# CVC_power.net
KiCad netlist of a schematic drawn in Altium Designer
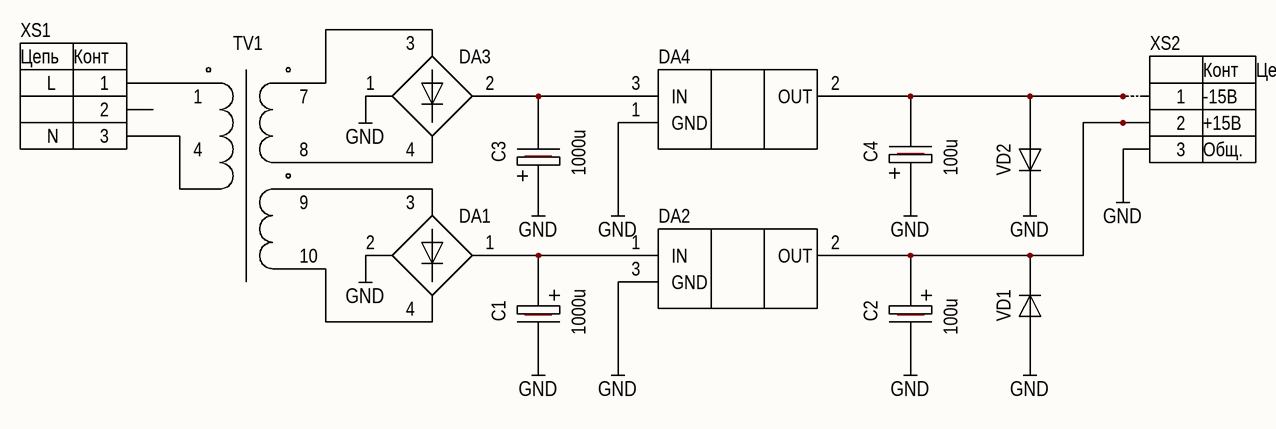
[diagram p0: CVC_power.SchDoc]

(export (version "E")
  (design (tool "Eeschema 10.0.6"))
  (components
    (comp (ref "C1")
      (value "Конденсатор К50-68")
      (footprint "CAPPR5-13x20")
      (description "Электролитический конденсатор")
      (fields (field (name "LABEL") "1000u"))
      (libsource (lib "") (part "Конденсатор К50-68_1"))
    )
    (comp (ref "C2")
      (value "Конденсатор К50-68")
      (footprint "CAPPR5-13x20")
      (description "Электролитический конденсатор")
      (fields (field (name "LABEL") "100u"))
      (libsource (lib "") (part "Конденсатор К50-68_1"))
    )
    (comp (ref "C3")
      (value "Конденсатор К50-68")
      (footprint "CAPPR5-13x20")
      (description "Электролитический конденсатор")
      (fields (field (name "LABEL") "1000u"))
      (libsource (lib "CVC_power") (part "Конденсатор К50-68"))
    )
    (comp (ref "C4")
      (value "Конденсатор К50-68")
      (footprint "CAPPR5-13x20")
      (description "Электролитический конденсатор")
      (fields (field (name "LABEL") "100u"))
      (libsource (lib "CVC_power") (part "Конденсатор К50-68"))
    )
    (comp (ref "DA1")
      (value "диодный мост")
      (footprint "DF08M")
      (libsource (lib "CVC_power") (part "Мост DB08M"))
    )
    (comp (ref "DA2")
      (value "L7815ACV")
      (footprint "TO220ABN")
      (libsource (lib "CVC_power") (part "L7815ACV"))
    )
    (comp (ref "DA3")
      (value "диодный мост")
      (footprint "DF08M")
      (libsource (lib "CVC_power") (part "Мост DB08M"))
    )
    (comp (ref "DA4") (value "L7915ACV") (footprint "TO220V") (libsource (lib "CVC_power") (part "L7915ACV")))
    (comp (ref "TV1")
      (value "Трансформатор ТП 112/ТПК-2")
      (footprint "Transformer TP 112/TPK - 2")
      (libsource (lib "CVC_power") (part "Трансформатор ТП 112/ТПК-2"))
    )
    (comp (ref "VD1") (value "1N4001") (footprint "DO-41") (libsource (lib "CVC_power") (part "1N4001")))
    (comp (ref "VD2") (value "1N4001") (footprint "DO-41") (libsource (lib "CVC_power") (part "1N4001")))
    (comp (ref "XS1")
      (value "Клемма 15EDGRC-3.81-03P (XY2500R)")
      (footprint "15EDGRC-3.81-03P")
      (libsource (lib "CVC_power") (part "Клемма 15EDGRC-3.81-03P (XY2500R)"))
    )
    (comp (ref "XS2")
      (value "Клемма 15EDGRC-3.81-03P (XY2500R)")
      (footprint "15EDGRC-3.81-03P")
      (libsource (lib "CVC_power") (part "Клемма 15EDGRC-3.81-03P (XY2500R)"))
    )
  )
  (nets
    (net (code "1") (name "+15V") (class "Default")
      (node (ref "C2") (pin "1") (pinfunction "+_1") (pintype "passive"))
      (node (ref "DA2") (pin "2") (pinfunction "OUT_2") (pintype "power_in"))
      (node (ref "VD1") (pin "2") (pinfunction "K_2") (pintype "passive"))
      (node (ref "XS2") (pin "2") (pinfunction "2_2") (pintype "passive"))
    )
    (net (code "2") (name "-15V") (class "Default")
      (node (ref "C4") (pin "2") (pinfunction "-_2") (pintype "passive"))
      (node (ref "DA4") (pin "2") (pinfunction "OUT_2") (pintype "power_in"))
      (node (ref "VD2") (pin "1") (pinfunction "A_1") (pintype "passive"))
      (node (ref "XS2") (pin "1") (pinfunction "1_1") (pintype "passive"))
    )
    (net (code "3") (name "GND") (class "Default")
      (node (ref "C1") (pin "2") (pinfunction "-_2") (pintype "passive"))
      (node (ref "C2") (pin "2") (pinfunction "-_2") (pintype "passive"))
      (node (ref "C3") (pin "1") (pinfunction "+_1") (pintype "passive"))
      (node (ref "C4") (pin "1") (pinfunction "+_1") (pintype "passive"))
      (node (ref "DA1") (pin "2") (pinfunction "-_2") (pintype "passive"))
      (node (ref "DA2") (pin "3") (pinfunction "GND_3") (pintype "power_in"))
      (node (ref "DA3") (pin "1") (pinfunction "+_1") (pintype "passive"))
      (node (ref "DA4") (pin "1") (pinfunction "GND_1") (pintype "power_in"))
      (node (ref "VD1") (pin "1") (pinfunction "A_1") (pintype "passive"))
      (node (ref "VD2") (pin "2") (pinfunction "K_2") (pintype "passive"))
      (node (ref "XS2") (pin "3") (pinfunction "3_3") (pintype "passive"))
    )
    (net (code "4") (name "Net-(C1-+)") (class "Default")
      (node (ref "C1") (pin "1") (pinfunction "+_1") (pintype "passive"))
      (node (ref "DA1") (pin "1") (pinfunction "+_1") (pintype "passive"))
      (node (ref "DA2") (pin "1") (pinfunction "IN_1") (pintype "power_in"))
    )
    (net (code "5") (name "Net-(C3--)") (class "Default")
      (node (ref "C3") (pin "2") (pinfunction "-_2") (pintype "passive"))
      (node (ref "DA3") (pin "2") (pinfunction "-_2") (pintype "passive"))
      (node (ref "DA4") (pin "3") (pinfunction "IN_3") (pintype "power_in"))
    )
    (net (code "6") (name "Net-(TV1-P1)") (class "Default")
      (node (ref "TV1") (pin "1") (pinfunction "P1_1") (pintype "passive"))
      (node (ref "XS1") (pin "1") (pinfunction "1_1") (pintype "passive"))
    )
    (net (code "7") (name "Net-(TV1-P4)") (class "Default")
      (node (ref "TV1") (pin "4") (pinfunction "P4_4") (pintype "passive"))
      (node (ref "XS1") (pin "3") (pinfunction "3_3") (pintype "passive"))
    )
    (net (code "8") (name "Net-(TV1-S7)") (class "Default")
      (node (ref "DA3") (pin "3") (pinfunction "~_3") (pintype "passive"))
      (node (ref "TV1") (pin "7") (pinfunction "S7_7") (pintype "passive"))
    )
    (net (code "9") (name "Net-(TV1-S8)") (class "Default")
      (node (ref "DA3") (pin "4") (pinfunction "~_4") (pintype "passive"))
      (node (ref "TV1") (pin "8") (pinfunction "S8_8") (pintype "passive"))
    )
    (net (code "10") (name "Net-(TV1-S9)") (class "Default")
      (node (ref "DA1") (pin "3") (pinfunction "~_3") (pintype "passive"))
      (node (ref "TV1") (pin "9") (pinfunction "S9_9") (pintype "passive"))
    )
    (net (code "11") (name "Net-(TV1-S10)") (class "Default")
      (node (ref "DA1") (pin "4") (pinfunction "~_4") (pintype "passive"))
      (node (ref "TV1") (pin "10") (pinfunction "S10_10") (pintype "passive"))
    )
    (net (code "12") (name "unconnected-(TV1-Pad2)") (class "Default")
      (node (ref "TV1") (pin "2") (pinfunction "2_2") (pintype "passive"))
    )
    (net (code "13") (name "unconnected-(TV1-Pad3)") (class "Default")
      (node (ref "TV1") (pin "3") (pinfunction "3_3") (pintype "passive"))
    )
    (net (code "14") (name "unconnected-(TV1-Pad5)") (class "Default")
      (node (ref "TV1") (pin "5") (pinfunction "5_5") (pintype "passive"))
    )
    (net (code "15") (name "unconnected-(TV1-Pad6)") (class "Default")
      (node (ref "TV1") (pin "6") (pinfunction "6_6") (pintype "passive"))
    )
    (net (code "16") (name "unconnected-(XS1-Pad2)") (class "Default")
      (node (ref "XS1") (pin "2") (pinfunction "2_2") (pintype "passive"))
    )
  )
)
